# PWM_Filter.net
KiCad netlist of a schematic drawn in Altium Designer
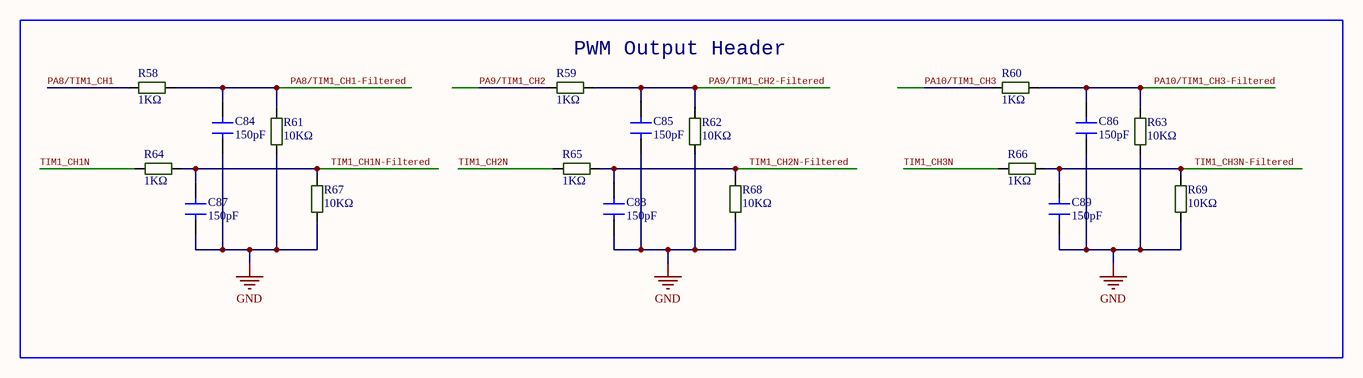
[diagram p0: PWM Filter.SchDoc]

(export (version "E")
  (design (tool "Eeschema 10.0.6"))
  (components
    (comp (ref "C84")
      (value "150pF")
      (footprint "C-0603W")
      (libsource (lib "Gate Driver Board") (part "C-0603"))
    )
    (comp (ref "C85")
      (value "150pF")
      (footprint "C-0603W")
      (libsource (lib "Gate Driver Board") (part "C-0603"))
    )
    (comp (ref "C86")
      (value "150pF")
      (footprint "C-0603W")
      (libsource (lib "Gate Driver Board") (part "C-0603"))
    )
    (comp (ref "C87")
      (value "150pF")
      (footprint "C-0603W")
      (libsource (lib "Gate Driver Board") (part "C-0603"))
    )
    (comp (ref "C88")
      (value "150pF")
      (footprint "C-0603W")
      (libsource (lib "Gate Driver Board") (part "C-0603"))
    )
    (comp (ref "C89")
      (value "150pF")
      (footprint "C-0603W")
      (libsource (lib "Gate Driver Board") (part "C-0603"))
    )
    (comp (ref "R58")
      (value "1KΩ")
      (footprint "R-0805")
      (libsource (lib "Gate Driver Board") (part "R-0805"))
    )
    (comp (ref "R59")
      (value "1KΩ")
      (footprint "R-0805")
      (libsource (lib "Gate Driver Board") (part "R-0805"))
    )
    (comp (ref "R60")
      (value "1KΩ")
      (footprint "R-0805")
      (libsource (lib "Gate Driver Board") (part "R-0805"))
    )
    (comp (ref "R61")
      (value "10KΩ")
      (footprint "R-0805")
      (libsource (lib "Gate Driver Board") (part "R-0805"))
    )
    (comp (ref "R62")
      (value "10KΩ")
      (footprint "R-0805")
      (libsource (lib "Gate Driver Board") (part "R-0805"))
    )
    (comp (ref "R63")
      (value "10KΩ")
      (footprint "R-0805")
      (libsource (lib "Gate Driver Board") (part "R-0805"))
    )
    (comp (ref "R64")
      (value "1KΩ")
      (footprint "R-0805")
      (libsource (lib "Gate Driver Board") (part "R-0805"))
    )
    (comp (ref "R65")
      (value "1KΩ")
      (footprint "R-0805")
      (libsource (lib "Gate Driver Board") (part "R-0805"))
    )
    (comp (ref "R66")
      (value "1KΩ")
      (footprint "R-0805")
      (libsource (lib "Gate Driver Board") (part "R-0805"))
    )
    (comp (ref "R67")
      (value "10KΩ")
      (footprint "R-0805")
      (libsource (lib "Gate Driver Board") (part "R-0805"))
    )
    (comp (ref "R68")
      (value "10KΩ")
      (footprint "R-0805")
      (libsource (lib "Gate Driver Board") (part "R-0805"))
    )
    (comp (ref "R69")
      (value "10KΩ")
      (footprint "R-0805")
      (libsource (lib "Gate Driver Board") (part "R-0805"))
    )
  )
  (nets
    (net (code "1") (name "/PA8{slash}TIM1_CH1") (class "Default")
      (node (ref "R58") (pin "1") (pinfunction "1_1") (pintype "passive"))
    )
    (net (code "2") (name "/PA8{slash}TIM1_CH1-Filtered") (class "Default")
      (node (ref "C84") (pin "2") (pinfunction "2_2") (pintype "passive"))
      (node (ref "R58") (pin "2") (pinfunction "2_2") (pintype "passive"))
      (node (ref "R61") (pin "2") (pinfunction "2_2") (pintype "passive"))
    )
    (net (code "3") (name "/PA9{slash}TIM1_CH2") (class "Default")
      (node (ref "R59") (pin "1") (pinfunction "1_1") (pintype "passive"))
    )
    (net (code "4") (name "/PA9{slash}TIM1_CH2-Filtered") (class "Default")
      (node (ref "C85") (pin "2") (pinfunction "2_2") (pintype "passive"))
      (node (ref "R59") (pin "2") (pinfunction "2_2") (pintype "passive"))
      (node (ref "R62") (pin "2") (pinfunction "2_2") (pintype "passive"))
    )
    (net (code "5") (name "/PA10{slash}TIM1_CH3") (class "Default")
      (node (ref "R60") (pin "1") (pinfunction "1_1") (pintype "passive"))
    )
    (net (code "6") (name "/PA10{slash}TIM1_CH3-Filtered") (class "Default")
      (node (ref "C86") (pin "2") (pinfunction "2_2") (pintype "passive"))
      (node (ref "R60") (pin "2") (pinfunction "2_2") (pintype "passive"))
      (node (ref "R63") (pin "2") (pinfunction "2_2") (pintype "passive"))
    )
    (net (code "7") (name "/TIM1_CH1N") (class "Default")
      (node (ref "R64") (pin "1") (pinfunction "1_1") (pintype "passive"))
    )
    (net (code "8") (name "/TIM1_CH1N-Filtered") (class "Default")
      (node (ref "C87") (pin "2") (pinfunction "2_2") (pintype "passive"))
      (node (ref "R64") (pin "2") (pinfunction "2_2") (pintype "passive"))
      (node (ref "R67") (pin "2") (pinfunction "2_2") (pintype "passive"))
    )
    (net (code "9") (name "/TIM1_CH2N") (class "Default")
      (node (ref "R65") (pin "1") (pinfunction "1_1") (pintype "passive"))
    )
    (net (code "10") (name "/TIM1_CH2N-Filtered") (class "Default")
      (node (ref "C88") (pin "2") (pinfunction "2_2") (pintype "passive"))
      (node (ref "R65") (pin "2") (pinfunction "2_2") (pintype "passive"))
      (node (ref "R68") (pin "2") (pinfunction "2_2") (pintype "passive"))
    )
    (net (code "11") (name "/TIM1_CH3N") (class "Default")
      (node (ref "R66") (pin "1") (pinfunction "1_1") (pintype "passive"))
    )
    (net (code "12") (name "/TIM1_CH3N-Filtered") (class "Default")
      (node (ref "C89") (pin "2") (pinfunction "2_2") (pintype "passive"))
      (node (ref "R66") (pin "2") (pinfunction "2_2") (pintype "passive"))
      (node (ref "R69") (pin "2") (pinfunction "2_2") (pintype "passive"))
    )
    (net (code "13") (name "GND") (class "Default")
      (node (ref "C84") (pin "1") (pinfunction "1_1") (pintype "passive"))
      (node (ref "C85") (pin "1") (pinfunction "1_1") (pintype "passive"))
      (node (ref "C86") (pin "1") (pinfunction "1_1") (pintype "passive"))
      (node (ref "C87") (pin "1") (pinfunction "1_1") (pintype "passive"))
      (node (ref "C88") (pin "1") (pinfunction "1_1") (pintype "passive"))
      (node (ref "C89") (pin "1") (pinfunction "1_1") (pintype "passive"))
      (node (ref "R61") (pin "1") (pinfunction "1_1") (pintype "passive"))
      (node (ref "R62") (pin "1") (pinfunction "1_1") (pintype "passive"))
      (node (ref "R63") (pin "1") (pinfunction "1_1") (pintype "passive"))
      (node (ref "R67") (pin "1") (pinfunction "1_1") (pintype "passive"))
      (node (ref "R68") (pin "1") (pinfunction "1_1") (pintype "passive"))
      (node (ref "R69") (pin "1") (pinfunction "1_1") (pintype "passive"))
    )
  )
)
